# Microphone1.net
KiCad netlist of a schematic drawn in Altium Designer
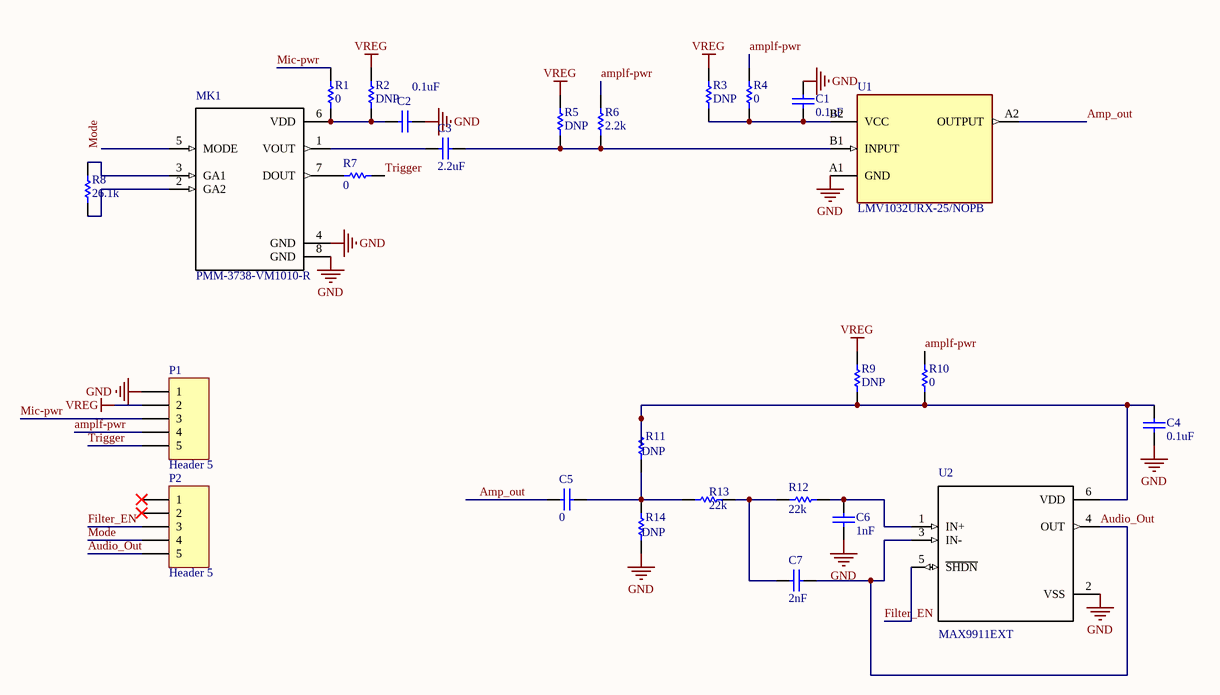
[diagram p0: Microphone1.SchDoc]

(export (version "E")
  (design (tool "Eeschema 10.0.6"))
  (components
    (comp (ref "C1")
      (value "0.1uF")
      (footprint "0402")
      (description "Ceramic Capacitor (Surface Mount)")
      (fields
        (field (name "DIGI-KEY PART NUMBER") "490-4759-1-ND")
        (field (name "MANUFACTURER") "Murata Electronics North America")
      )
      (libsource (lib "WISP_AD10") (part "Cap"))
    )
    (comp (ref "C2")
      (value "0.1uF")
      (footprint "0402")
      (description "Ceramic Capacitor (Surface Mount)")
      (fields
        (field (name "DIGI-KEY PART NUMBER") "490-4759-1-ND")
        (field (name "MANUFACTURER") "Murata Electronics North America")
      )
      (libsource (lib "WISP_AD10") (part "Cap"))
    )
    (comp (ref "C3")
      (value "2.2uF")
      (footprint "0402")
      (description "Ceramic Capacitor (Surface Mount)")
      (fields (field (name "DIGI-KEY PART NUMBER") "311-0.0JRCT-ND") (field (name "MANUFACTURER") "Yageo"))
      (libsource (lib "WISP_AD10") (part "Cap"))
    )
    (comp (ref "C4")
      (value "0.1uF")
      (footprint "0402")
      (description "Ceramic Capacitor (Surface Mount)")
      (fields
        (field (name "DIGI-KEY PART NUMBER") "490-4759-1-ND")
        (field (name "MANUFACTURER") "Murata Electronics North America")
      )
      (libsource (lib "WISP_AD10") (part "Cap"))
    )
    (comp (ref "C5")
      (value "0")
      (footprint "0402")
      (description "Ceramic Capacitor (Surface Mount)")
      (fields (field (name "DIGI-KEY PART NUMBER") "311-0.0JRCT-ND") (field (name "MANUFACTURER") "Yageo"))
      (libsource (lib "WISP_AD10") (part "Cap"))
    )
    (comp (ref "C6")
      (value "1nF")
      (footprint "0402")
      (description "Ceramic Capacitor (Surface Mount)")
      (fields
        (field (name "DIGI-KEY PART NUMBER") "490-4761-1-ND")
        (field (name "MANUFACTURER") "Murata Electronics")
      )
      (libsource (lib "WISP_AD10") (part "Cap"))
    )
    (comp (ref "C7")
      (value "2nF")
      (footprint "0402")
      (description "Ceramic Capacitor (Surface Mount)")
      (fields
        (field (name "DIGI-KEY PART NUMBER") "478-10122-1-ND")
        (field (name "MANUFACTURER") "AVX Corporation")
      )
      (libsource (lib "WISP_AD10") (part "Cap"))
    )
    (comp (ref "MK1")
      (value "PMM-3738-VM1010-R")
      (footprint "MIC_PMM-3738-VM1010-R")
      (description "MEMS Microphone Omni-Directional 700 Ohm -38dBV 1.8V Rectangular Solder Pad T/R")
      (fields
        (field (name "MANUFACTURER PART NUMBER") "VM1010")
        (field (name "MANUFACTURER") "Vesper Technologies Inc.")
      )
      (libsource (lib "BLE") (part "PMM-3738-VM1010-R"))
    )
    (comp (ref "P1")
      (value "Header 5")
      (footprint "HDR1X5")
      (description "Header, 5-Pin")
      (fields (field (name "PUBLISHER") "Altium Limited"))
      (libsource (lib "Miscellaneous Connectors") (part "Header 5"))
    )
    (comp (ref "P2")
      (value "Header 5")
      (footprint "HDR1X5")
      (description "Header, 5-Pin")
      (fields (field (name "PUBLISHER") "Altium Limited"))
      (libsource (lib "Miscellaneous Connectors") (part "Header 5"))
    )
    (comp (ref "R1")
      (value "0")
      (footprint "0402")
      (description "Chip Resistor (Surface Mount)")
      (fields (field (name "MANUFACTURER") "Generic Chip Res (TBD)"))
      (libsource (lib "WISP_AD10") (part "Res"))
    )
    (comp (ref "R2")
      (value "DNP")
      (footprint "0402")
      (description "Chip Resistor (Surface Mount)")
      (fields (field (name "MANUFACTURER") "Generic Chip Res (TBD)") (field (name "Comment") "Res"))
      (libsource (lib "WISP_AD10") (part "Res"))
    )
    (comp (ref "R3")
      (value "DNP")
      (footprint "0402")
      (description "Chip Resistor (Surface Mount)")
      (fields
        (field (name "MANUFACTURER") "Yageo")
        (field (name "MANUFACTURER PART NUMBER") "RC0402JR-070RL")
      )
      (libsource (lib "WISP_AD10") (part "Res"))
    )
    (comp (ref "R4")
      (value "0")
      (footprint "0402")
      (description "Chip Resistor (Surface Mount)")
      (fields
        (field (name "MANUFACTURER") "Yageo")
        (field (name "MANUFACTURER PART NUMBER") "RC0402JR-070RL")
      )
      (libsource (lib "WISP_AD10") (part "Res"))
    )
    (comp (ref "R5")
      (value "DNP")
      (footprint "0402")
      (description "Chip Resistor (Surface Mount)")
      (fields
        (field (name "MANUFACTURER") "Yageo")
        (field (name "MANUFACTURER PART NUMBER") "RC0402JR-070RL")
      )
      (libsource (lib "WISP_AD10") (part "Res"))
    )
    (comp (ref "R6")
      (value "2.2k")
      (footprint "0402")
      (description "Chip Resistor (Surface Mount)")
      (fields
        (field (name "MANUFACTURER") "Yageo")
        (field (name "MANUFACTURER PART NUMBER") "RC0402JR-070RL")
      )
      (libsource (lib "WISP_AD10") (part "Res"))
    )
    (comp (ref "R7")
      (value "0")
      (footprint "0402")
      (description "Chip Resistor (Surface Mount)")
      (fields
        (field (name "MANUFACTURER") "Yageo")
        (field (name "MANUFACTURER PART NUMBER") "RC0402JR-070RL")
      )
      (libsource (lib "WISP_AD10") (part "Res"))
    )
    (comp (ref "R8")
      (value "26.1k")
      (footprint "0402")
      (description "Chip Resistor (Surface Mount)")
      (fields
        (field (name "MANUFACTURER") "Yageo")
        (field (name "MANUFACTURER PART NUMBER") "RC0402FR-0726K1L")
      )
      (libsource (lib "WISP_AD10") (part "Res"))
    )
    (comp (ref "R9")
      (value "DNP")
      (footprint "0402")
      (description "Chip Resistor (Surface Mount)")
      (fields
        (field (name "MANUFACTURER") "Yageo")
        (field (name "MANUFACTURER PART NUMBER") "RC0402JR-070RL")
      )
      (libsource (lib "WISP_AD10") (part "Res"))
    )
    (comp (ref "R10")
      (value "0")
      (footprint "0402")
      (description "Chip Resistor (Surface Mount)")
      (fields
        (field (name "MANUFACTURER") "Yageo")
        (field (name "MANUFACTURER PART NUMBER") "RC0402JR-070RL")
      )
      (libsource (lib "WISP_AD10") (part "Res"))
    )
    (comp (ref "R11")
      (value "DNP")
      (footprint "0402")
      (description "Chip Resistor (Surface Mount)")
      (fields
        (field (name "MANUFACTURER") "Yageo")
        (field (name "MANUFACTURER PART NUMBER") "RC0402FR-071ML")
      )
      (libsource (lib "WISP_AD10") (part "Res"))
    )
    (comp (ref "R12")
      (value "22k")
      (footprint "0402")
      (description "Chip Resistor (Surface Mount)")
      (fields
        (field (name "MANUFACTURER") "Yageo")
        (field (name "MANUFACTURER PART NUMBER") "RT0402BRD0722KL")
      )
      (libsource (lib "WISP_AD10") (part "Res"))
    )
    (comp (ref "R13")
      (value "22k")
      (footprint "0402")
      (description "Chip Resistor (Surface Mount)")
      (fields
        (field (name "MANUFACTURER") "Yageo")
        (field (name "MANUFACTURER PART NUMBER") "RT0402BRD0722KL")
      )
      (libsource (lib "WISP_AD10") (part "Res"))
    )
    (comp (ref "R14")
      (value "DNP")
      (footprint "0402")
      (description "Chip Resistor (Surface Mount)")
      (fields
        (field (name "MANUFACTURER") "Yageo")
        (field (name "MANUFACTURER PART NUMBER") "RC0402FR-071ML")
      )
      (libsource (lib "WISP_AD10") (part "Res"))
    )
    (comp (ref "U1")
      (value "LMV1032URX-25/NOPB")
      (footprint "BGA4C2X2X50P_117X117X42")
      (description "Analog input microphone preamplifier for 3-wire electret microphones")
      (fields (field (name "MF") "Texas Instruments"))
      (libsource (lib "LMV1032URX-25_NOPB") (part "LMV1032URX-25/NOPB"))
    )
    (comp (ref "U2")
      (value "MAX9911EXT")
      (footprint "MAX9911EXT")
      (description "Operational amplifier; 1.8Ã·5.5VDC; Channels: 1; SC70-6")
      (fields (field (name "MANUFACTURER PART NUMBER") "MAX9911EXT+T") (field (name "MANUFACTURER") "Maxim"))
      (libsource (lib "BLE") (part "MAX9911EXT"))
    )
  )
  (nets
    (net (code "1") (name "/Amp_out") (class "Default")
      (node (ref "C5") (pin "1") (pinfunction "1_1") (pintype "passive"))
      (node (ref "U1") (pin "A2") (pinfunction "OUTPUT_A2") (pintype "output"))
    )
    (net (code "2") (name "/Audio_Out") (class "Default")
      (node (ref "C7") (pin "1") (pinfunction "1_1") (pintype "passive"))
      (node (ref "P2") (pin "5") (pinfunction "5_5") (pintype "passive"))
      (node (ref "U2") (pin "3") (pinfunction "IN-_3") (pintype "input"))
      (node (ref "U2") (pin "4") (pinfunction "OUT_4") (pintype "output"))
    )
    (net (code "3") (name "/Filter_EN") (class "Default")
      (node (ref "P2") (pin "3") (pinfunction "3_3") (pintype "passive"))
      (node (ref "U2") (pin "5") (pinfunction "~{SHDN}_5") (pintype "bidirectional"))
    )
    (net (code "4") (name "/Mic-pwr") (class "Default")
      (node (ref "P1") (pin "3") (pinfunction "3_3") (pintype "passive"))
      (node (ref "R1") (pin "2") (pinfunction "2_2") (pintype "passive"))
    )
    (net (code "5") (name "/Mode") (class "Default")
      (node (ref "MK1") (pin "5") (pinfunction "MODE_5") (pintype "input"))
      (node (ref "P2") (pin "4") (pinfunction "4_4") (pintype "passive"))
    )
    (net (code "6") (name "/Trigger") (class "Default")
      (node (ref "P1") (pin "5") (pinfunction "5_5") (pintype "passive"))
      (node (ref "R7") (pin "2") (pinfunction "2_2") (pintype "passive"))
    )
    (net (code "7") (name "/amplf-pwr") (class "Default")
      (node (ref "P1") (pin "4") (pinfunction "4_4") (pintype "passive"))
      (node (ref "R10") (pin "1") (pinfunction "1_1") (pintype "passive"))
      (node (ref "R4") (pin "1") (pinfunction "1_1") (pintype "passive"))
      (node (ref "R6") (pin "1") (pinfunction "1_1") (pintype "passive"))
    )
    (net (code "8") (name "GND") (class "Default")
      (node (ref "C1") (pin "2") (pinfunction "2_2") (pintype "passive"))
      (node (ref "C2") (pin "2") (pinfunction "2_2") (pintype "passive"))
      (node (ref "C4") (pin "1") (pinfunction "1_1") (pintype "passive"))
      (node (ref "C6") (pin "2") (pinfunction "2_2") (pintype "passive"))
      (node (ref "MK1") (pin "4") (pinfunction "GND_4") (pintype "power_in"))
      (node (ref "MK1") (pin "8") (pinfunction "GND_8") (pintype "power_in"))
      (node (ref "P1") (pin "1") (pinfunction "1_1") (pintype "passive"))
      (node (ref "R14") (pin "1") (pinfunction "1_1") (pintype "passive"))
      (node (ref "U1") (pin "A1") (pinfunction "GND_A1") (pintype "passive"))
      (node (ref "U2") (pin "2") (pinfunction "VSS_2") (pintype "power_in"))
    )
    (net (code "9") (name "Net-(C5-Pad2)") (class "Default")
      (node (ref "C5") (pin "2") (pinfunction "2_2") (pintype "passive"))
      (node (ref "R11") (pin "1") (pinfunction "1_1") (pintype "passive"))
      (node (ref "R13") (pin "1") (pinfunction "1_1") (pintype "passive"))
      (node (ref "R14") (pin "2") (pinfunction "2_2") (pintype "passive"))
    )
    (net (code "10") (name "Net-(C7-Pad2)") (class "Default")
      (node (ref "C7") (pin "2") (pinfunction "2_2") (pintype "passive"))
      (node (ref "R12") (pin "1") (pinfunction "1_1") (pintype "passive"))
      (node (ref "R13") (pin "2") (pinfunction "2_2") (pintype "passive"))
    )
    (net (code "11") (name "Net-(MK1-DOUT)") (class "Default")
      (node (ref "MK1") (pin "7") (pinfunction "DOUT_7") (pintype "output"))
      (node (ref "R7") (pin "1") (pinfunction "1_1") (pintype "passive"))
    )
    (net (code "12") (name "Net-(MK1-GA1)") (class "Default")
      (node (ref "MK1") (pin "3") (pinfunction "GA1_3") (pintype "input"))
      (node (ref "R8") (pin "1") (pinfunction "1_1") (pintype "passive"))
    )
    (net (code "13") (name "Net-(MK1-GA2)") (class "Default")
      (node (ref "MK1") (pin "2") (pinfunction "GA2_2") (pintype "input"))
      (node (ref "R8") (pin "2") (pinfunction "2_2") (pintype "passive"))
    )
    (net (code "14") (name "Net-(MK1-VDD)") (class "Default")
      (node (ref "C2") (pin "1") (pinfunction "1_1") (pintype "passive"))
      (node (ref "MK1") (pin "6") (pinfunction "VDD_6") (pintype "power_in"))
      (node (ref "R1") (pin "1") (pinfunction "1_1") (pintype "passive"))
      (node (ref "R2") (pin "1") (pinfunction "1_1") (pintype "passive"))
    )
    (net (code "15") (name "Net-(MK1-VOUT)") (class "Default")
      (node (ref "C3") (pin "1") (pinfunction "1_1") (pintype "passive"))
      (node (ref "MK1") (pin "1") (pinfunction "VOUT_1") (pintype "output"))
    )
    (net (code "16") (name "Net-(U1-INPUT)") (class "Default")
      (node (ref "C3") (pin "2") (pinfunction "2_2") (pintype "passive"))
      (node (ref "R5") (pin "2") (pinfunction "2_2") (pintype "passive"))
      (node (ref "R6") (pin "2") (pinfunction "2_2") (pintype "passive"))
      (node (ref "U1") (pin "B1") (pinfunction "INPUT_B1") (pintype "input"))
    )
    (net (code "17") (name "Net-(U1-VCC)") (class "Default")
      (node (ref "C1") (pin "1") (pinfunction "1_1") (pintype "passive"))
      (node (ref "R3") (pin "2") (pinfunction "2_2") (pintype "passive"))
      (node (ref "R4") (pin "2") (pinfunction "2_2") (pintype "passive"))
      (node (ref "U1") (pin "B2") (pinfunction "VCC_B2") (pintype "power_in"))
    )
    (net (code "18") (name "Net-(U2-IN+)") (class "Default")
      (node (ref "C6") (pin "1") (pinfunction "1_1") (pintype "passive"))
      (node (ref "R12") (pin "2") (pinfunction "2_2") (pintype "passive"))
      (node (ref "U2") (pin "1") (pinfunction "IN+_1") (pintype "input"))
    )
    (net (code "19") (name "Net-(U2-VDD)") (class "Default")
      (node (ref "C4") (pin "2") (pinfunction "2_2") (pintype "passive"))
      (node (ref "R10") (pin "2") (pinfunction "2_2") (pintype "passive"))
      (node (ref "R11") (pin "2") (pinfunction "2_2") (pintype "passive"))
      (node (ref "R9") (pin "2") (pinfunction "2_2") (pintype "passive"))
      (node (ref "U2") (pin "6") (pinfunction "VDD_6") (pintype "power_in"))
    )
    (net (code "20") (name "VREG") (class "Default")
      (node (ref "P1") (pin "2") (pinfunction "2_2") (pintype "passive"))
      (node (ref "R2") (pin "2") (pinfunction "2_2") (pintype "passive"))
      (node (ref "R3") (pin "1") (pinfunction "1_1") (pintype "passive"))
      (node (ref "R5") (pin "1") (pinfunction "1_1") (pintype "passive"))
      (node (ref "R9") (pin "1") (pinfunction "1_1") (pintype "passive"))
    )
    (net (code "21") (name "unconnected-(P2-Pad1)") (class "Default")
      (node (ref "P2") (pin "1") (pinfunction "1_1") (pintype "passive+no_connect"))
    )
    (net (code "22") (name "unconnected-(P2-Pad2)") (class "Default")
      (node (ref "P2") (pin "2") (pinfunction "2_2") (pintype "passive+no_connect"))
    )
  )
)
